# thermal-stock.net
KiCad netlist of a schematic drawn in EAGLE
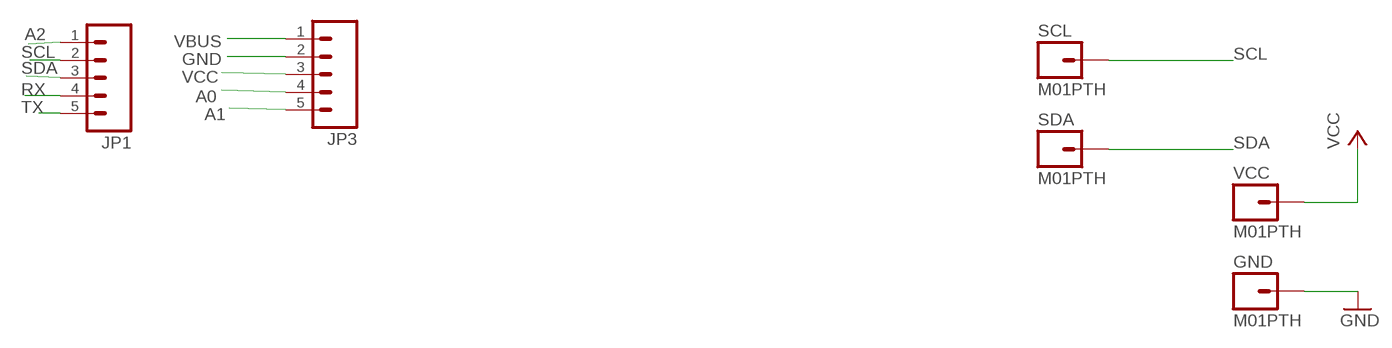
[diagram p0: schematic, sheet 1]

(export (version "E")
  (design (tool "Eeschema 10.0.6"))
  (components
    (comp (ref "GND")
      (value "M01PTH")
      (footprint "eagle-import:1X01")
      (libsource (lib "eagle-import") (part "M01PTH"))
    )
    (comp (ref "JP1")
      (value "M05LOCK")
      (footprint "eagle-import:1X05_LOCK")
      (libsource (lib "eagle-import") (part "M05LOCK"))
    )
    (comp (ref "JP3")
      (value "M05LOCK")
      (footprint "eagle-import:1X05_LOCK")
      (libsource (lib "eagle-import") (part "M05LOCK"))
    )
    (comp (ref "SCL")
      (value "M01PTH")
      (footprint "eagle-import:1X01")
      (libsource (lib "eagle-import") (part "M01PTH"))
    )
    (comp (ref "SDA")
      (value "M01PTH")
      (footprint "eagle-import:1X01")
      (libsource (lib "eagle-import") (part "M01PTH"))
    )
    (comp (ref "VCC")
      (value "M01PTH")
      (footprint "eagle-import:1X01")
      (libsource (lib "eagle-import") (part "M01PTH"))
    )
  )
  (nets
    (net (code "1") (name "/A0") (class "Default")
      (node (ref "JP3") (pin "4") (pinfunction "4_4") (pintype "passive"))
    )
    (net (code "2") (name "/A1") (class "Default")
      (node (ref "JP3") (pin "5") (pinfunction "5_5") (pintype "passive"))
    )
    (net (code "3") (name "/A2") (class "Default")
      (node (ref "JP1") (pin "1") (pinfunction "1_1") (pintype "passive"))
    )
    (net (code "4") (name "/RX") (class "Default")
      (node (ref "JP1") (pin "4") (pinfunction "4_4") (pintype "passive"))
    )
    (net (code "5") (name "/SCL") (class "Default")
      (node (ref "JP1") (pin "2") (pinfunction "2_2") (pintype "passive"))
      (node (ref "SCL") (pin "1") (pinfunction "1_1") (pintype "passive"))
    )
    (net (code "6") (name "/SDA") (class "Default")
      (node (ref "JP1") (pin "3") (pinfunction "3_3") (pintype "passive"))
      (node (ref "SDA") (pin "1") (pinfunction "1_1") (pintype "passive"))
    )
    (net (code "7") (name "/TX") (class "Default")
      (node (ref "JP1") (pin "5") (pinfunction "5_5") (pintype "passive"))
    )
    (net (code "8") (name "/VBUS") (class "Default")
      (node (ref "JP3") (pin "1") (pinfunction "1_1") (pintype "passive"))
    )
    (net (code "9") (name "GND") (class "Default")
      (node (ref "GND") (pin "1") (pinfunction "1_1") (pintype "passive"))
      (node (ref "JP3") (pin "2") (pinfunction "2_2") (pintype "passive"))
    )
    (net (code "10") (name "VCC") (class "Default")
      (node (ref "JP3") (pin "3") (pinfunction "3_3") (pintype "passive"))
      (node (ref "VCC") (pin "1") (pinfunction "1_1") (pintype "passive"))
    )
  )
)
